# USBSocket_Type9_v1_0.net
KiCad netlist of a schematic drawn in EAGLE
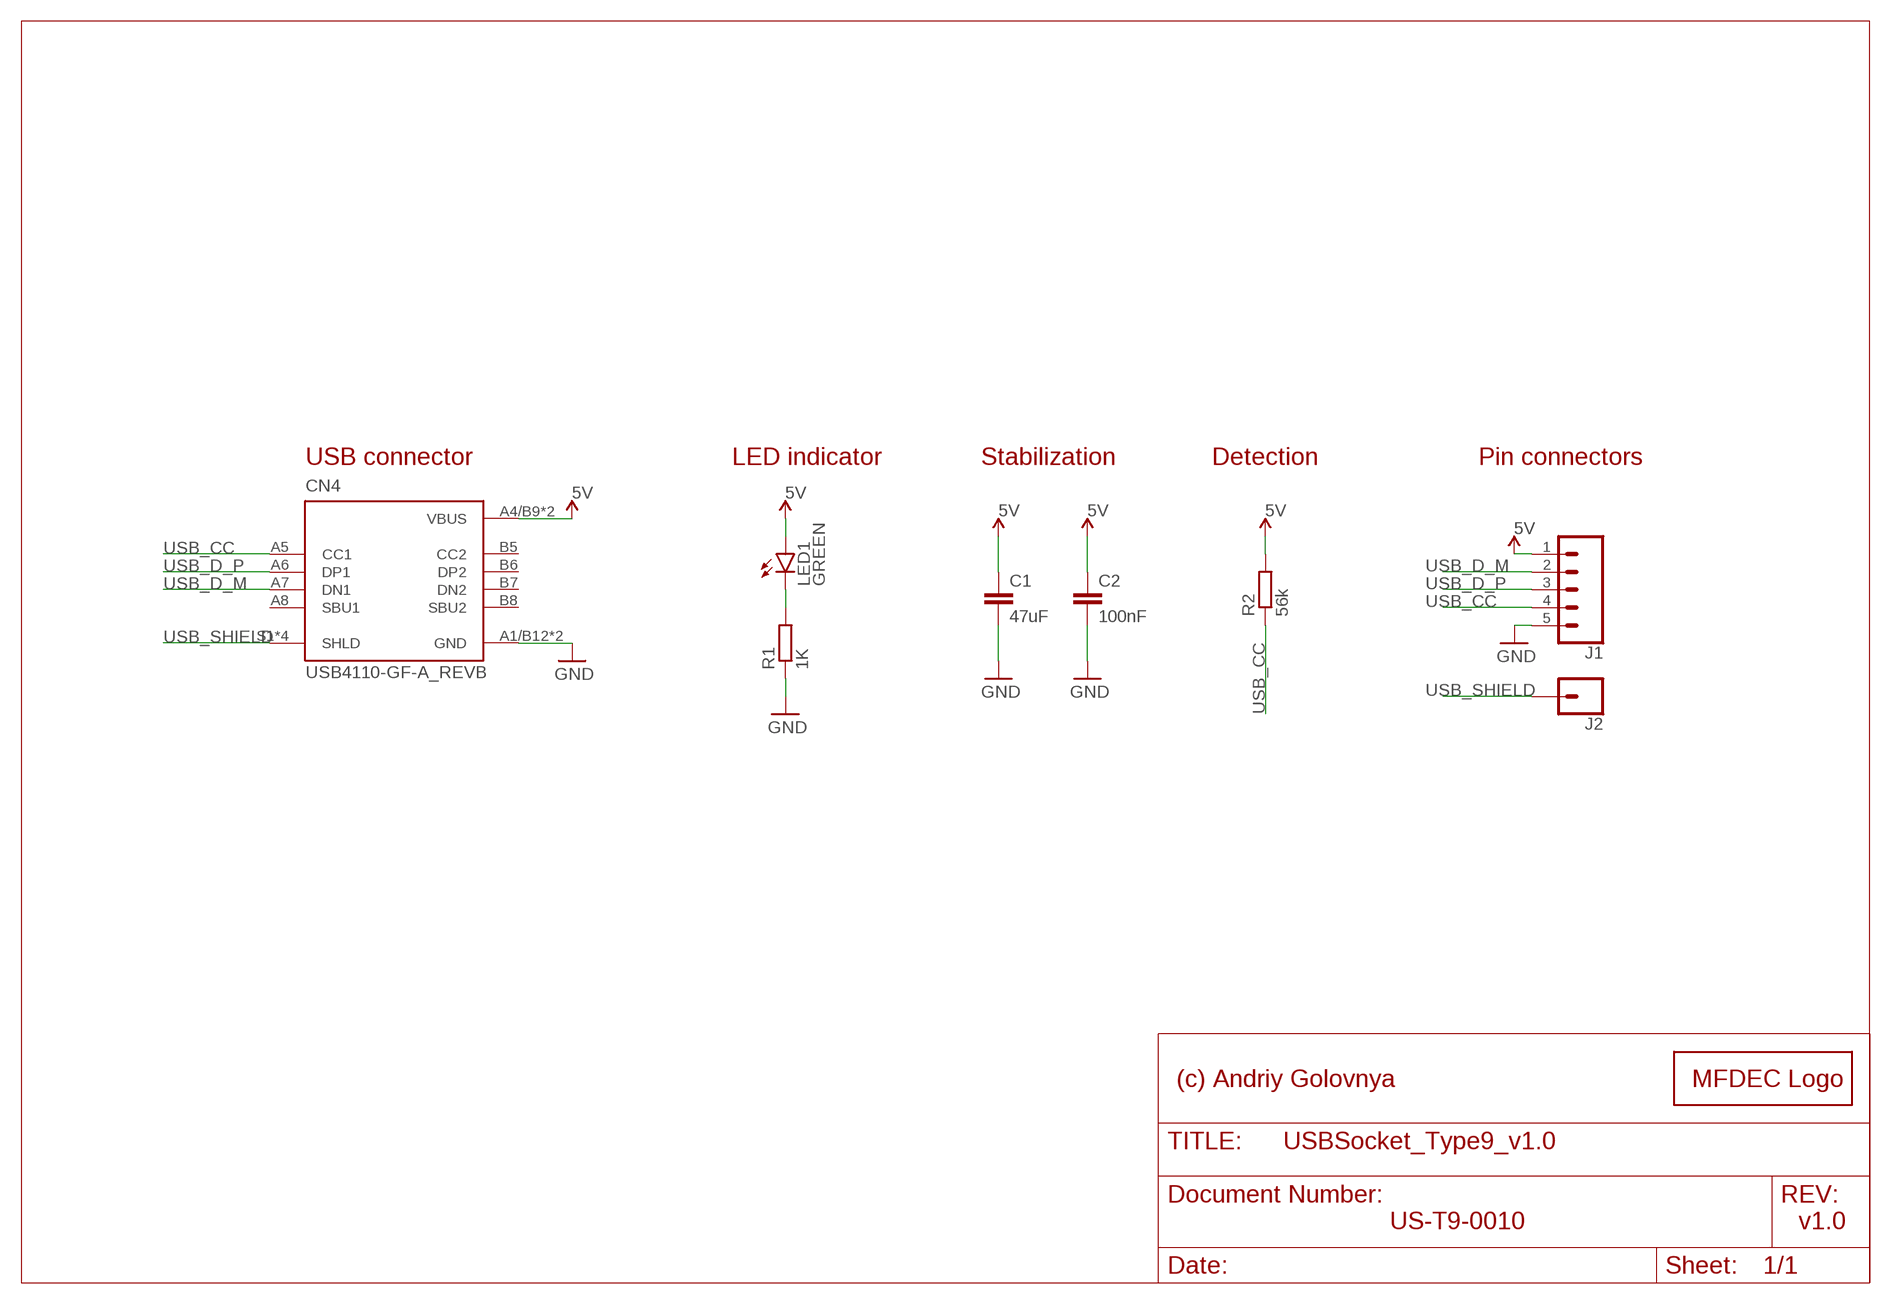
[diagram p0: schematic, sheet 1]

(export (version "E")
  (design (tool "Eeschema 10.0.6"))
  (components
    (comp (ref "C1")
      (value "47uF")
      (footprint "eagle-import:C0805")
      (libsource (lib "eagle-import") (part "C-EUC0805"))
    )
    (comp (ref "C2")
      (value "100nF")
      (footprint "eagle-import:C0402")
      (libsource (lib "eagle-import") (part "C-EUC0402"))
    )
    (comp (ref "CN4")
      (value "USB4110-GF-A_REVB")
      (footprint "eagle-import:GCT_USB4110-GF-A_REVB")
      (fields (field (name "MF") "GCT") (field (name "MP") "USB4110-GF-A"))
      (libsource (lib "eagle-import") (part "USB4110-GF-A_REVB"))
    )
    (comp (ref "J1")
      (value "CONN_05PTH")
      (footprint "eagle-import:1X05")
      (libsource (lib "eagle-import") (part "CONN_05PTH"))
    )
    (comp (ref "J2")
      (value "CONN_01")
      (footprint "eagle-import:1X01")
      (libsource (lib "eagle-import") (part "CONN_01"))
    )
    (comp (ref "LED1")
      (value "GREEN")
      (footprint "eagle-import:SML0603")
      (libsource (lib "eagle-import") (part "LEDSML0603"))
    )
    (comp (ref "LOGO1")
      (value "MFDECLOGO_L_10MM")
      (footprint "eagle-import:MFDEC_L_10MM")
      (libsource (lib "eagle-import") (part "MFDECLOGO_L_10MM"))
    )
    (comp (ref "R1")
      (value "1K")
      (footprint "eagle-import:R0402")
      (libsource (lib "eagle-import") (part "R-EU_R0402"))
    )
    (comp (ref "R2")
      (value "56k")
      (footprint "eagle-import:R0402")
      (libsource (lib "eagle-import") (part "R-EU_R0402"))
    )
  )
  (nets
    (net (code "1") (name "/USB_CC") (class "Default")
      (node (ref "CN4") (pin "A5") (pinfunction "CC1_A5") (pintype "bidirectional"))
      (node (ref "J1") (pin "4") (pinfunction "4_4") (pintype "passive"))
      (node (ref "R2") (pin "1") (pinfunction "1_1") (pintype "passive"))
    )
    (net (code "2") (name "/USB_D_M") (class "Default")
      (node (ref "CN4") (pin "A7") (pinfunction "DN1_A7") (pintype "bidirectional"))
      (node (ref "J1") (pin "2") (pinfunction "2_2") (pintype "passive"))
    )
    (net (code "3") (name "/USB_D_P") (class "Default")
      (node (ref "CN4") (pin "A6") (pinfunction "DP1_A6") (pintype "bidirectional"))
      (node (ref "J1") (pin "3") (pinfunction "3_3") (pintype "passive"))
    )
    (net (code "4") (name "/USB_SHIELD") (class "Default")
      (node (ref "CN4") (pin "S1") (pinfunction "SHLD_S1") (pintype "bidirectional"))
      (node (ref "CN4") (pin "S2") (pinfunction "SHLD_S2") (pintype "bidirectional"))
      (node (ref "CN4") (pin "S3") (pinfunction "SHLD_S3") (pintype "bidirectional"))
      (node (ref "CN4") (pin "S4") (pinfunction "SHLD_S4") (pintype "bidirectional"))
      (node (ref "J2") (pin "1") (pinfunction "1_1") (pintype "passive"))
    )
    (net (code "5") (name "5V") (class "Default")
      (node (ref "C1") (pin "1") (pinfunction "1_1") (pintype "passive"))
      (node (ref "C2") (pin "1") (pinfunction "1_1") (pintype "passive"))
      (node (ref "CN4") (pin "A4/B9") (pinfunction "VBUS_A4/B9") (pintype "power_in"))
      (node (ref "CN4") (pin "B4/A9") (pinfunction "VBUS_B4/A9") (pintype "power_in"))
      (node (ref "J1") (pin "1") (pinfunction "1_1") (pintype "passive"))
      (node (ref "LED1") (pin "A") (pinfunction "A_A") (pintype "passive"))
      (node (ref "R2") (pin "2") (pinfunction "2_2") (pintype "passive"))
    )
    (net (code "6") (name "GND") (class "Default")
      (node (ref "C1") (pin "2") (pinfunction "2_2") (pintype "passive"))
      (node (ref "C2") (pin "2") (pinfunction "2_2") (pintype "passive"))
      (node (ref "CN4") (pin "A1/B12") (pinfunction "GND_A1/B12") (pintype "power_in"))
      (node (ref "CN4") (pin "B1/A12") (pinfunction "GND_B1/A12") (pintype "power_in"))
      (node (ref "J1") (pin "5") (pinfunction "5_5") (pintype "passive"))
      (node (ref "R1") (pin "1") (pinfunction "1_1") (pintype "passive"))
    )
    (net (code "7") (name "Net-(LED1-PadC)") (class "Default")
      (node (ref "LED1") (pin "C") (pinfunction "C_C") (pintype "passive"))
      (node (ref "R1") (pin "2") (pinfunction "2_2") (pintype "passive"))
    )
    (net (code "8") (name "unconnected-(CN4-CC2-PadB5)") (class "Default")
      (node (ref "CN4") (pin "B5") (pinfunction "CC2_B5") (pintype "bidirectional"))
    )
    (net (code "9") (name "unconnected-(CN4-DN2-PadB7)") (class "Default")
      (node (ref "CN4") (pin "B7") (pinfunction "DN2_B7") (pintype "bidirectional"))
    )
    (net (code "10") (name "unconnected-(CN4-DP2-PadB6)") (class "Default")
      (node (ref "CN4") (pin "B6") (pinfunction "DP2_B6") (pintype "bidirectional"))
    )
    (net (code "11") (name "unconnected-(CN4-SBU1-PadA8)") (class "Default")
      (node (ref "CN4") (pin "A8") (pinfunction "SBU1_A8") (pintype "bidirectional"))
    )
    (net (code "12") (name "unconnected-(CN4-SBU2-PadB8)") (class "Default")
      (node (ref "CN4") (pin "B8") (pinfunction "SBU2_B8") (pintype "bidirectional"))
    )
  )
)
